# SPI_IFC.net
KiCad netlist of a schematic drawn in Altium Designer
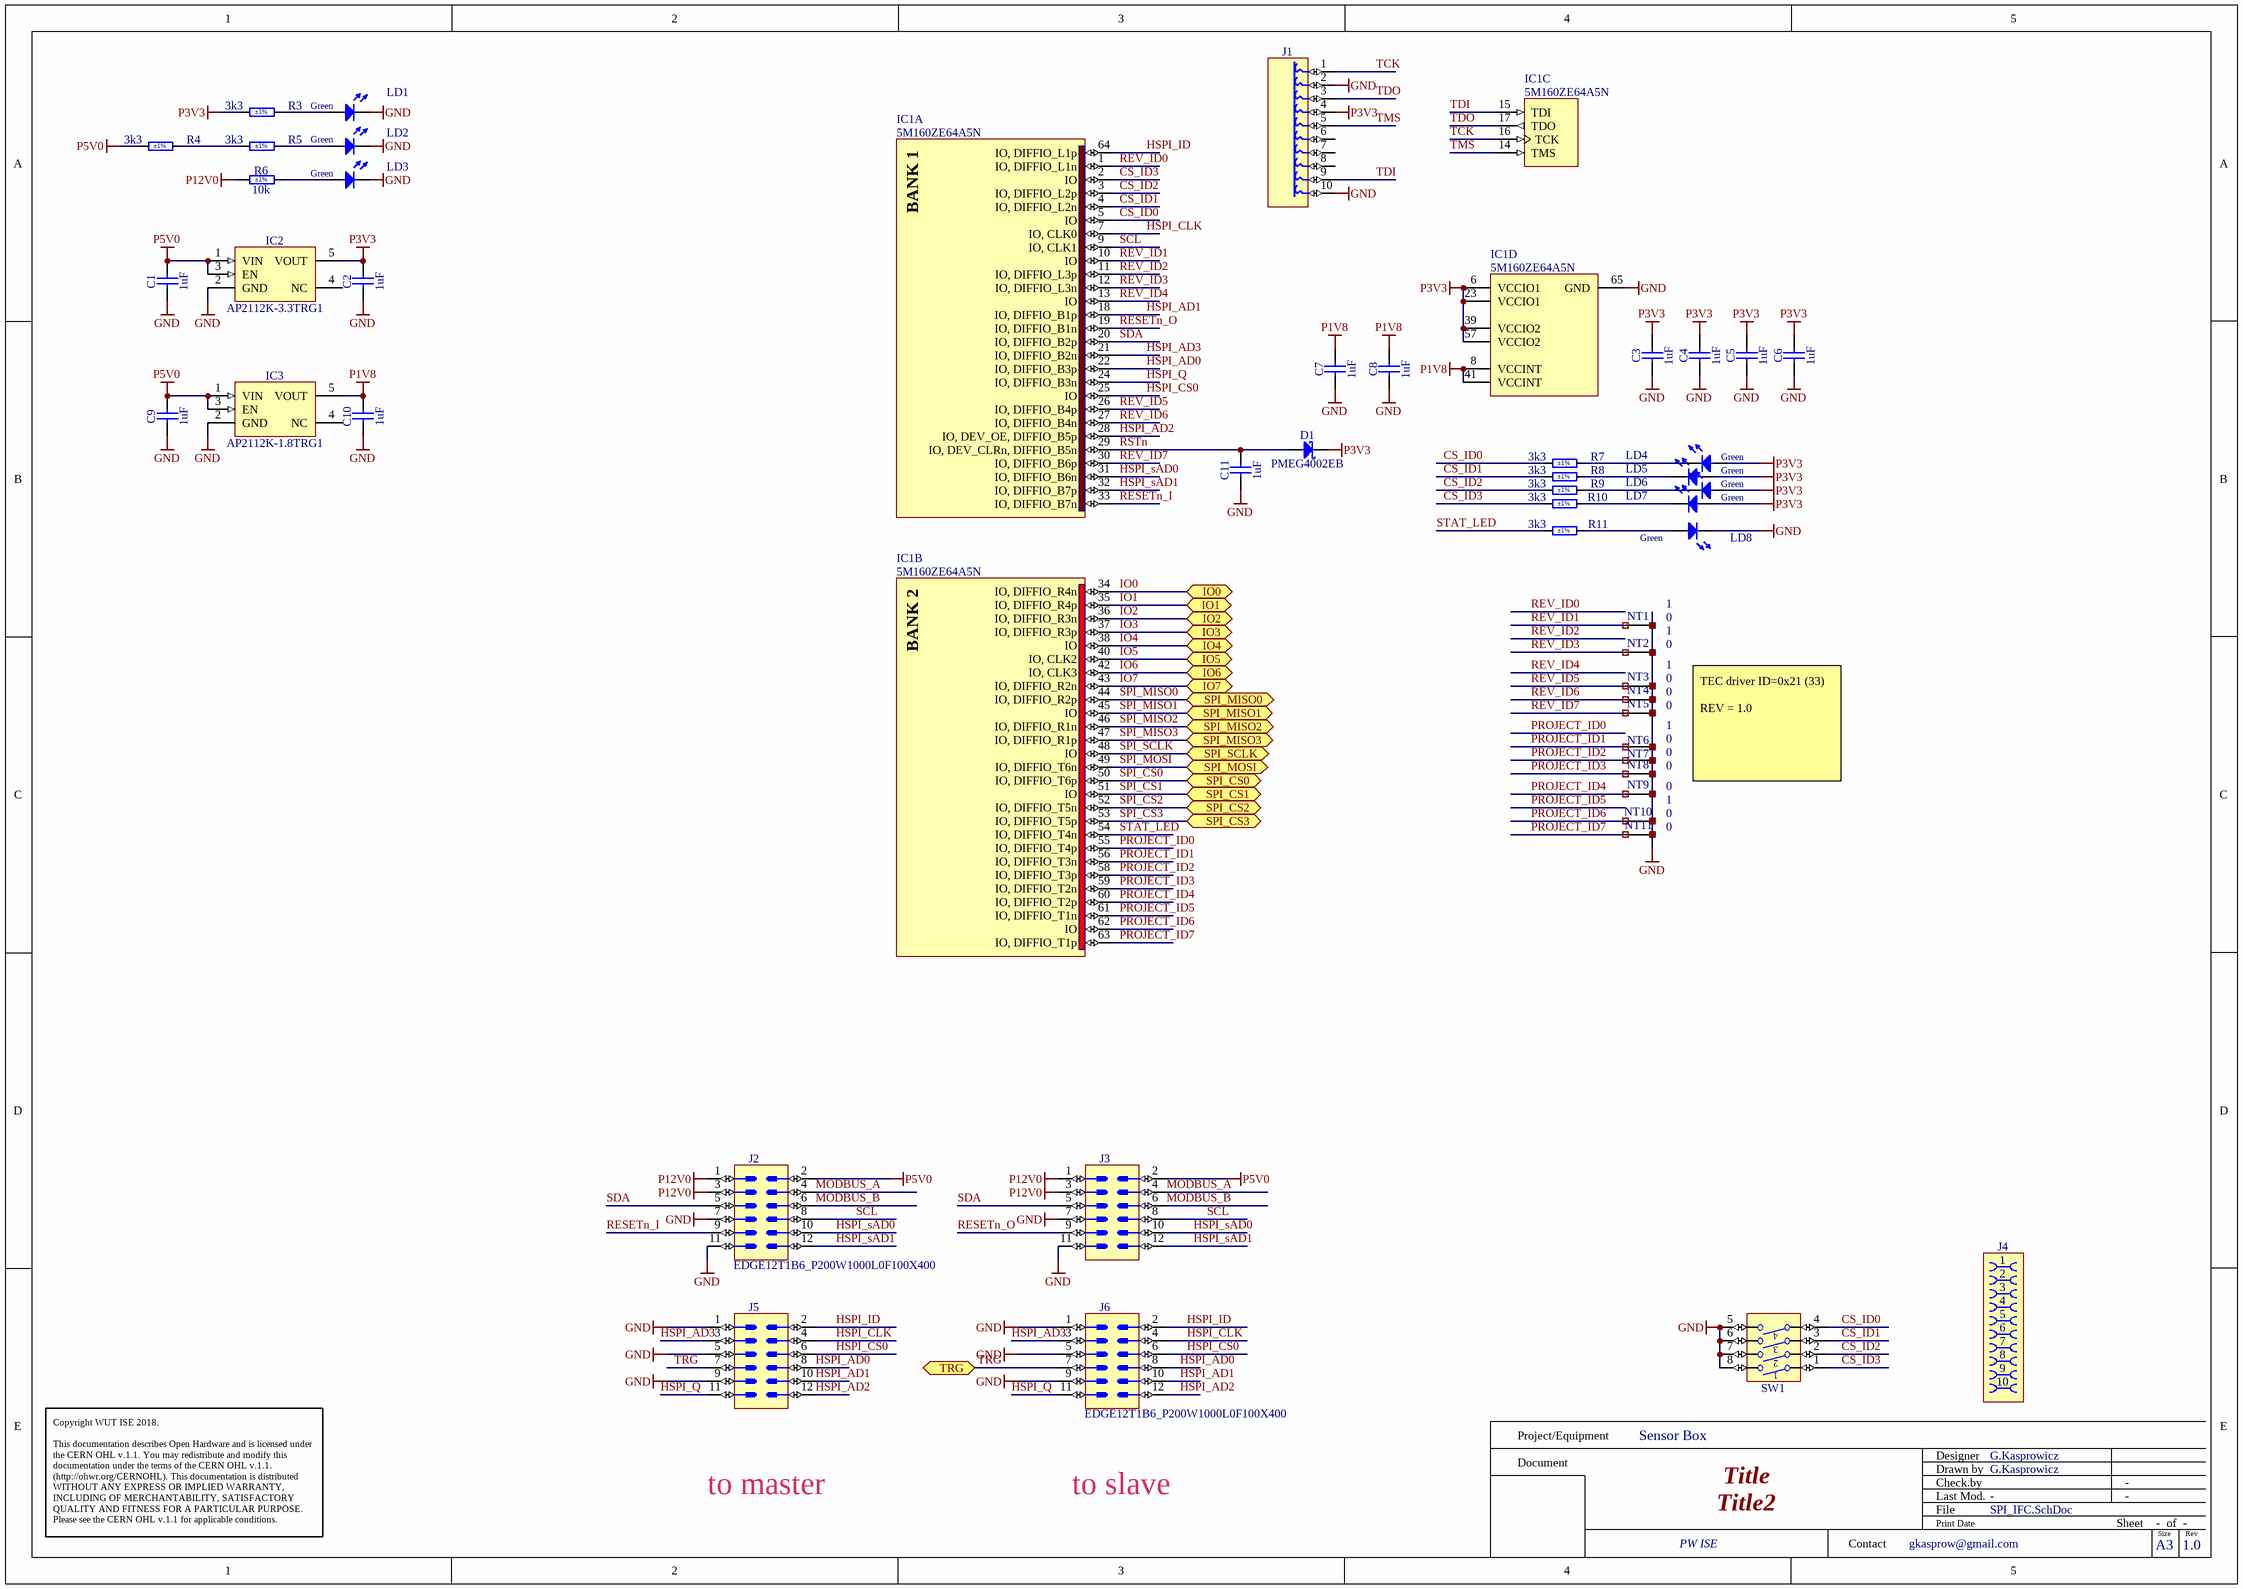
[diagram p0: SPI_IFC.SchDoc]

(export (version "E")
  (design (tool "Eeschema 10.0.6"))
  (components
    (comp (ref "C1")
      (value "1uF")
      (footprint "CAPC1005X55N")
      (description "Non-polarised capacitor")
      (fields
        (field (name "PART NUMBER") "CC0402_1UF_16V_10%_X5R")
        (field (name "VOLTAGE") "16V")
        (field (name "AUTHOR") "CERN DEM JLC")
      )
      (libsource (lib "Capacitors") (part "Capacitor - non polarized"))
    )
    (comp (ref "C2")
      (value "1uF")
      (footprint "CAPC1005X55N")
      (description "Non-polarised capacitor")
      (fields
        (field (name "PART NUMBER") "CC0402_1UF_16V_10%_X5R")
        (field (name "VOLTAGE") "16V")
        (field (name "AUTHOR") "CERN DEM JLC")
      )
      (libsource (lib "Capacitors") (part "Capacitor - non polarized"))
    )
    (comp (ref "C3")
      (value "1uF")
      (footprint "CAPC1005X55N")
      (description "Non-polarised capacitor")
      (fields
        (field (name "PART NUMBER") "CC0402_1UF_16V_10%_X5R")
        (field (name "VOLTAGE") "16V")
        (field (name "AUTHOR") "CERN DEM JLC")
      )
      (libsource (lib "Capacitors") (part "Capacitor - non polarized"))
    )
    (comp (ref "C4")
      (value "1uF")
      (footprint "CAPC1005X55N")
      (description "Non-polarised capacitor")
      (fields
        (field (name "PART NUMBER") "CC0402_1UF_16V_10%_X5R")
        (field (name "VOLTAGE") "16V")
        (field (name "AUTHOR") "CERN DEM JLC")
      )
      (libsource (lib "Capacitors") (part "Capacitor - non polarized"))
    )
    (comp (ref "C5")
      (value "1uF")
      (footprint "CAPC1005X55N")
      (description "Non-polarised capacitor")
      (fields
        (field (name "PART NUMBER") "CC0402_1UF_16V_10%_X5R")
        (field (name "VOLTAGE") "16V")
        (field (name "AUTHOR") "CERN DEM JLC")
      )
      (libsource (lib "Capacitors") (part "Capacitor - non polarized"))
    )
    (comp (ref "C6")
      (value "1uF")
      (footprint "CAPC1005X55N")
      (description "Non-polarised capacitor")
      (fields
        (field (name "PART NUMBER") "CC0402_1UF_16V_10%_X5R")
        (field (name "VOLTAGE") "16V")
        (field (name "AUTHOR") "CERN DEM JLC")
      )
      (libsource (lib "Capacitors") (part "Capacitor - non polarized"))
    )
    (comp (ref "C7")
      (value "1uF")
      (footprint "CAPC1005X55N")
      (description "Non-polarised capacitor")
      (fields
        (field (name "PART NUMBER") "CC0402_1UF_16V_10%_X5R")
        (field (name "VOLTAGE") "16V")
        (field (name "AUTHOR") "CERN DEM JLC")
      )
      (libsource (lib "Capacitors") (part "Capacitor - non polarized"))
    )
    (comp (ref "C8")
      (value "1uF")
      (footprint "CAPC1005X55N")
      (description "Non-polarised capacitor")
      (fields
        (field (name "PART NUMBER") "CC0402_1UF_16V_10%_X5R")
        (field (name "VOLTAGE") "16V")
        (field (name "AUTHOR") "CERN DEM JLC")
      )
      (libsource (lib "Capacitors") (part "Capacitor - non polarized"))
    )
    (comp (ref "C9")
      (value "1uF")
      (footprint "CAPC1005X55N")
      (description "Non-polarised capacitor")
      (fields
        (field (name "PART NUMBER") "CC0402_1UF_16V_10%_X5R")
        (field (name "VOLTAGE") "16V")
        (field (name "AUTHOR") "CERN DEM JLC")
      )
      (libsource (lib "Capacitors") (part "Capacitor - non polarized"))
    )
    (comp (ref "C10")
      (value "1uF")
      (footprint "CAPC1005X55N")
      (description "Non-polarised capacitor")
      (fields
        (field (name "PART NUMBER") "CC0402_1UF_16V_10%_X5R")
        (field (name "VOLTAGE") "16V")
        (field (name "AUTHOR") "CERN DEM JLC")
      )
      (libsource (lib "Capacitors") (part "Capacitor - non polarized"))
    )
    (comp (ref "C11")
      (value "1uF")
      (footprint "CAPC1005X55N")
      (description "Non-polarised capacitor")
      (fields
        (field (name "PART NUMBER") "CC0402_1UF_16V_10%_X5R")
        (field (name "VOLTAGE") "16V")
        (field (name "AUTHOR") "CERN DEM JLC")
      )
      (libsource (lib "Capacitors") (part "Capacitor - non polarized"))
    )
    (comp (ref "D1")
      (value "PMEG4002EB")
      (footprint "SODFL1608X65N")
      (description "Schottky Diode")
      (fields
        (field (name "VOLTAGE") "40V")
        (field (name "POWER") "200mA")
        (field (name "AUTHOR") "CERN DEM JMW")
      )
      (libsource (lib "ICs And Semiconductors") (part "Diode Schottky"))
    )
    (comp (ref "IC1")
      (value "5M160ZE64A5N")
      (footprint "QFP40P900X900X120-65N-S550")
      (fields (field (name "MANUFACTURER") "ALTERA") (field (name "AUTHOR") "CERN DEM JLC"))
      (libsource (lib "ICs And Semiconductors") (part "5M160ZE64A5N"))
    )
    (comp (ref "IC2")
      (value "AP2112K-3.3TRG1")
      (footprint "SOT95P285X140-5N")
      (description "600mA CMOS Low Dropout Linear Regulator with Enable")
      (fields
        (field (name "MANUFACTURER") "DIODES INCORPORATED")
        (field (name "MANUFACTURER PART NUMBER") "AP2112K-3.3")
        (field (name "AUTHOR") "CERN DEM MR")
      )
      (libsource (lib "ICs And Semiconductors") (part "AP2112K"))
    )
    (comp (ref "IC3")
      (value "AP2112K-1.8TRG1")
      (footprint "SOT95P285X140-5N")
      (description "600mA CMOS Low Dropout Linear Regulator with Enable")
      (fields
        (field (name "MANUFACTURER") "DIODES INCORPORATED")
        (field (name "MANUFACTURER PART NUMBER") "AP2112K-1.8")
        (field (name "AUTHOR") "CERN DEM JLC")
      )
      (libsource (lib "ICs And Semiconductors") (part "AP2112K"))
    )
    (comp (ref "J1")
      (value "TC2050-IDC")
      (footprint "TC2050-IDC")
      (description "TC2030-MCP and TC2050-IDC Pad Contact")
      (fields (field (name "AUTHOR") "CERN DEM HF"))
      (libsource (lib "Eletro-mechanical") (part "TC2050-IDC"))
    )
    (comp (ref "J2")
      (value "~")
      (footprint "EDGE12T1B6_P200W1000L0F100X400")
      (description "PCB Edge Connector 12 (2x6)")
      (fields
        (field (name "PART NUMBER") "EDGE10T1B6_P200W1000L0F100X400")
        (field (name "AUTHOR") "CERN DEM MR")
      )
      (libsource (lib "Connectors") (part "PCB Edge Connector 12 (2x6)"))
    )
    (comp (ref "J3")
      (value "~")
      (footprint "EDGE12T5B10_P200W1000L0F100X400")
      (description "PCB Edge Connector 12 (2x6)")
      (fields (field (name "PART NUMBER") "EDGE12T5B10_P200W1000L0F100X400") (field (name "AUTHOR") "GK"))
      (libsource (lib "Connectors") (part "PCB Edge Connector 12 (2x6) R"))
    )
    (comp (ref "J4")
      (value "~")
      (footprint "AVX_00 9159 010 061 916")
      (description "Open Ended Card Edge Connector, 9159 Series")
      (fields
        (field (name "PART NUMBER") "AVX_00 9159 010 061 916")
        (field (name "MANUFACTURER") "AVX")
        (field (name "AUTHOR") "CERN DEM MR")
      )
      (libsource (lib "Connectors") (part "AVX_00 9159 010 061 916"))
    )
    (comp (ref "J5")
      (value "~")
      (footprint "EDGE12T5B10_P200W1000L0F100X400")
      (description "PCB Edge Connector 12 (2x6)")
      (fields (field (name "PART NUMBER") "EDGE12T5B10_P200W1000L0F100X400") (field (name "AUTHOR") "GK"))
      (libsource (lib "Connectors") (part "PCB Edge Connector 12 (2x6) R"))
    )
    (comp (ref "J6")
      (value "~")
      (footprint "EDGE12T1B6_P200W1000L0F100X400")
      (description "PCB Edge Connector 12 (2x6)")
      (fields
        (field (name "PART NUMBER") "EDGE10T1B6_P200W1000L0F100X400")
        (field (name "AUTHOR") "CERN DEM MR")
      )
      (libsource (lib "Connectors") (part "PCB Edge Connector 12 (2x6)"))
    )
    (comp (ref "LD1")
      (value "Green")
      (footprint "LED_KINGBRIGHT_KP-1608CGCK")
      (description "LED Green 1C 2A")
      (fields
        (field (name "PART NUMBER") "LED_KINGBRIGHT_KP-1608CGCK")
        (field (name "MANUFACTURER") "KINGBRIGHT")
        (field (name "AUTHOR") "CERN DEM HF")
      )
      (libsource (lib "ICs And Semiconductors") (part "LED Green 1C 2A"))
    )
    (comp (ref "LD2")
      (value "Green")
      (footprint "LED_KINGBRIGHT_KP-1608CGCK")
      (description "LED Green 1C 2A")
      (fields
        (field (name "PART NUMBER") "LED_KINGBRIGHT_KP-1608CGCK")
        (field (name "MANUFACTURER") "KINGBRIGHT")
        (field (name "AUTHOR") "CERN DEM HF")
      )
      (libsource (lib "ICs And Semiconductors") (part "LED Green 1C 2A"))
    )
    (comp (ref "LD3")
      (value "Green")
      (footprint "LED_KINGBRIGHT_KP-1608CGCK")
      (description "LED Green 1C 2A")
      (fields
        (field (name "PART NUMBER") "LED_KINGBRIGHT_KP-1608CGCK")
        (field (name "MANUFACTURER") "KINGBRIGHT")
        (field (name "AUTHOR") "CERN DEM HF")
      )
      (libsource (lib "ICs And Semiconductors") (part "LED Green 1C 2A"))
    )
    (comp (ref "LD4")
      (value "Green")
      (footprint "LED_KINGBRIGHT_KP-1608CGCK")
      (description "LED Green 1C 2A")
      (fields
        (field (name "PART NUMBER") "LED_KINGBRIGHT_KP-1608CGCK")
        (field (name "MANUFACTURER") "KINGBRIGHT")
        (field (name "AUTHOR") "CERN DEM HF")
      )
      (libsource (lib "ICs And Semiconductors") (part "LED Green 1C 2A"))
    )
    (comp (ref "LD5")
      (value "Green")
      (footprint "LED_KINGBRIGHT_KP-1608CGCK")
      (description "LED Green 1C 2A")
      (fields
        (field (name "PART NUMBER") "LED_KINGBRIGHT_KP-1608CGCK")
        (field (name "MANUFACTURER") "KINGBRIGHT")
        (field (name "AUTHOR") "CERN DEM HF")
      )
      (libsource (lib "ICs And Semiconductors") (part "LED Green 1C 2A"))
    )
    (comp (ref "LD6")
      (value "Green")
      (footprint "LED_KINGBRIGHT_KP-1608CGCK")
      (description "LED Green 1C 2A")
      (fields
        (field (name "PART NUMBER") "LED_KINGBRIGHT_KP-1608CGCK")
        (field (name "MANUFACTURER") "KINGBRIGHT")
        (field (name "AUTHOR") "CERN DEM HF")
      )
      (libsource (lib "ICs And Semiconductors") (part "LED Green 1C 2A"))
    )
    (comp (ref "LD7")
      (value "Green")
      (footprint "LED_KINGBRIGHT_KP-1608CGCK")
      (description "LED Green 1C 2A")
      (fields
        (field (name "PART NUMBER") "LED_KINGBRIGHT_KP-1608CGCK")
        (field (name "MANUFACTURER") "KINGBRIGHT")
        (field (name "AUTHOR") "CERN DEM HF")
      )
      (libsource (lib "ICs And Semiconductors") (part "LED Green 1C 2A"))
    )
    (comp (ref "LD8")
      (value "Green")
      (footprint "LED_KINGBRIGHT_KP-1608CGCK")
      (description "LED Green 1C 2A")
      (fields
        (field (name "PART NUMBER") "LED_KINGBRIGHT_KP-1608CGCK")
        (field (name "MANUFACTURER") "KINGBRIGHT")
        (field (name "AUTHOR") "CERN DEM HF")
      )
      (libsource (lib "ICs And Semiconductors") (part "LED Green 1C 2A"))
    )
    (comp (ref "NT1")
      (value "Net Tie")
      (footprint "Net Tie 3")
      (fields (field (name "PART NUMBER") "Net Tie 3") (field (name "AUTHOR") "CERN DEM HF"))
      (libsource (lib "Eletro-mechanical") (part "Net Tie_a"))
    )
    (comp (ref "NT2")
      (value "Net Tie")
      (footprint "Net Tie 3")
      (fields (field (name "PART NUMBER") "Net Tie 3") (field (name "AUTHOR") "CERN DEM HF"))
      (libsource (lib "Eletro-mechanical") (part "Net Tie_a"))
    )
    (comp (ref "NT3")
      (value "Net Tie")
      (footprint "Net Tie 3")
      (fields (field (name "PART NUMBER") "Net Tie 3") (field (name "AUTHOR") "CERN DEM HF"))
      (libsource (lib "Eletro-mechanical") (part "Net Tie_a"))
    )
    (comp (ref "NT4")
      (value "Net Tie")
      (footprint "Net Tie 3")
      (fields (field (name "PART NUMBER") "Net Tie 3") (field (name "AUTHOR") "CERN DEM HF"))
      (libsource (lib "Eletro-mechanical") (part "Net Tie_a"))
    )
    (comp (ref "NT5")
      (value "Net Tie")
      (footprint "Net Tie 3")
      (fields (field (name "PART NUMBER") "Net Tie 3") (field (name "AUTHOR") "CERN DEM HF"))
      (libsource (lib "Eletro-mechanical") (part "Net Tie_a"))
    )
    (comp (ref "NT6")
      (value "Net Tie")
      (footprint "Net Tie 3")
      (fields (field (name "PART NUMBER") "Net Tie 3") (field (name "AUTHOR") "CERN DEM HF"))
      (libsource (lib "Eletro-mechanical") (part "Net Tie_a"))
    )
    (comp (ref "NT7")
      (value "Net Tie")
      (footprint "Net Tie 3")
      (fields (field (name "PART NUMBER") "Net Tie 3") (field (name "AUTHOR") "CERN DEM HF"))
      (libsource (lib "Eletro-mechanical") (part "Net Tie_a"))
    )
    (comp (ref "NT8")
      (value "Net Tie")
      (footprint "Net Tie 3")
      (fields (field (name "PART NUMBER") "Net Tie 3") (field (name "AUTHOR") "CERN DEM HF"))
      (libsource (lib "Eletro-mechanical") (part "Net Tie_a"))
    )
    (comp (ref "NT9")
      (value "Net Tie")
      (footprint "Net Tie 3")
      (fields (field (name "PART NUMBER") "Net Tie 3") (field (name "AUTHOR") "CERN DEM HF"))
      (libsource (lib "Eletro-mechanical") (part "Net Tie_a"))
    )
    (comp (ref "NT10")
      (value "Net Tie")
      (footprint "Net Tie 3")
      (fields (field (name "PART NUMBER") "Net Tie 3") (field (name "AUTHOR") "CERN DEM HF"))
      (libsource (lib "Eletro-mechanical") (part "Net Tie_a"))
    )
    (comp (ref "NT11")
      (value "Net Tie")
      (footprint "Net Tie 3")
      (fields (field (name "PART NUMBER") "Net Tie 3") (field (name "AUTHOR") "CERN DEM HF"))
      (libsource (lib "Eletro-mechanical") (part "Net Tie_a"))
    )
    (comp (ref "R3")
      (value "3k3")
      (footprint "RESC1005X40N")
      (description "Resistor - 1%")
      (fields
        (field (name "TOLERANCE") "±1%")
        (field (name "PART NUMBER") "R0402_3K3_1%_0.0625W_100PPM")
        (field (name "POWER") "0.0625W")
        (field (name "AUTHOR") "CERN DEM JLC")
      )
      (libsource (lib "Resistors") (part "Resistor - 1%"))
    )
    (comp (ref "R4")
      (value "3k3")
      (footprint "RESC1005X40N")
      (description "Resistor - 1%")
      (fields
        (field (name "TOLERANCE") "±1%")
        (field (name "PART NUMBER") "R0402_3K3_1%_0.0625W_100PPM")
        (field (name "POWER") "0.0625W")
        (field (name "AUTHOR") "CERN DEM JLC")
      )
      (libsource (lib "Resistors") (part "Resistor - 1%"))
    )
    (comp (ref "R5")
      (value "3k3")
      (footprint "RESC1005X40N")
      (description "Resistor - 1%")
      (fields
        (field (name "TOLERANCE") "±1%")
        (field (name "PART NUMBER") "R0402_3K3_1%_0.0625W_100PPM")
        (field (name "POWER") "0.0625W")
        (field (name "AUTHOR") "CERN DEM JLC")
      )
      (libsource (lib "Resistors") (part "Resistor - 1%"))
    )
    (comp (ref "R6")
      (value "10k")
      (footprint "RESC1005X40N")
      (description "Resistor - 1%")
      (fields
        (field (name "TOLERANCE") "±1%")
        (field (name "PART NUMBER") "R0402_10K_1%_0.0625W_100PPM")
        (field (name "POWER") "0.0625W")
        (field (name "AUTHOR") "CERN DEM JLC")
      )
      (libsource (lib "Resistors") (part "Resistor - 1%"))
    )
    (comp (ref "R7")
      (value "3k3")
      (footprint "RESC1005X40N")
      (description "Resistor - 1%")
      (fields
        (field (name "TOLERANCE") "±1%")
        (field (name "PART NUMBER") "R0402_3K3_1%_0.0625W_100PPM")
        (field (name "POWER") "0.0625W")
        (field (name "AUTHOR") "CERN DEM JLC")
      )
      (libsource (lib "Resistors") (part "Resistor - 1%"))
    )
    (comp (ref "R8")
      (value "3k3")
      (footprint "RESC1005X40N")
      (description "Resistor - 1%")
      (fields
        (field (name "TOLERANCE") "±1%")
        (field (name "PART NUMBER") "R0402_3K3_1%_0.0625W_100PPM")
        (field (name "POWER") "0.0625W")
        (field (name "AUTHOR") "CERN DEM JLC")
      )
      (libsource (lib "Resistors") (part "Resistor - 1%"))
    )
    (comp (ref "R9")
      (value "3k3")
      (footprint "RESC1005X40N")
      (description "Resistor - 1%")
      (fields
        (field (name "TOLERANCE") "±1%")
        (field (name "PART NUMBER") "R0402_3K3_1%_0.0625W_100PPM")
        (field (name "POWER") "0.0625W")
        (field (name "AUTHOR") "CERN DEM JLC")
      )
      (libsource (lib "Resistors") (part "Resistor - 1%"))
    )
    (comp (ref "R10")
      (value "3k3")
      (footprint "RESC1005X40N")
      (description "Resistor - 1%")
      (fields
        (field (name "TOLERANCE") "±1%")
        (field (name "PART NUMBER") "R0402_3K3_1%_0.0625W_100PPM")
        (field (name "POWER") "0.0625W")
        (field (name "AUTHOR") "CERN DEM JLC")
      )
      (libsource (lib "Resistors") (part "Resistor - 1%"))
    )
    (comp (ref "R11")
      (value "3k3")
      (footprint "RESC1005X40N")
      (description "Resistor - 1%")
      (fields
        (field (name "TOLERANCE") "±1%")
        (field (name "PART NUMBER") "R0402_3K3_1%_0.0625W_100PPM")
        (field (name "POWER") "0.0625W")
        (field (name "AUTHOR") "CERN DEM JLC")
      )
      (libsource (lib "Resistors") (part "Resistor - 1%"))
    )
    (comp (ref "SW1")
      (value "Switch")
      (footprint "SW_OMRON_A6H-4102")
      (description "4 Ways SPST DIP Switch")
      (fields
        (field (name "PART NUMBER") "SW_OMRON_A6H-4102")
        (field (name "MANUFACTURER") "OMRON")
        (field (name "AUTHOR") "CERN DEM JLC")
      )
      (libsource (lib "Eletro-mechanical") (part "SW 4x SPST DIP Switch"))
    )
  )
  (nets
    (net (code "1") (name "/CS_ID0") (class "Default")
      (node (ref "IC1") (pin "5") (pinfunction "IO_5") (pintype "bidirectional"))
      (node (ref "R7") (pin "2") (pinfunction "2_2") (pintype "passive"))
      (node (ref "SW1") (pin "4") (pinfunction "4_4") (pintype "bidirectional"))
    )
    (net (code "2") (name "/CS_ID1") (class "Default")
      (node (ref "IC1") (pin "4") (pinfunction "IO,_DIFFIO_L2n_4") (pintype "bidirectional"))
      (node (ref "R8") (pin "2") (pinfunction "2_2") (pintype "passive"))
      (node (ref "SW1") (pin "3") (pinfunction "3_3") (pintype "bidirectional"))
    )
    (net (code "3") (name "/CS_ID2") (class "Default")
      (node (ref "IC1") (pin "3") (pinfunction "IO,_DIFFIO_L2p_3") (pintype "bidirectional"))
      (node (ref "R9") (pin "2") (pinfunction "2_2") (pintype "passive"))
      (node (ref "SW1") (pin "2") (pinfunction "2_2") (pintype "bidirectional"))
    )
    (net (code "4") (name "/CS_ID3") (class "Default")
      (node (ref "IC1") (pin "2") (pinfunction "IO_2") (pintype "bidirectional"))
      (node (ref "R10") (pin "2") (pinfunction "2_2") (pintype "passive"))
      (node (ref "SW1") (pin "1") (pinfunction "1_1") (pintype "bidirectional"))
    )
    (net (code "5") (name "/HSPI_AD0") (class "Default")
      (node (ref "IC1") (pin "22") (pinfunction "IO,_DIFFIO_B3p_22") (pintype "bidirectional"))
      (node (ref "J5") (pin "8") (pinfunction "8_8") (pintype "bidirectional"))
      (node (ref "J6") (pin "8") (pinfunction "8_8") (pintype "bidirectional"))
    )
    (net (code "6") (name "/HSPI_AD1") (class "Default")
      (node (ref "IC1") (pin "18") (pinfunction "IO,_DIFFIO_B1p_18") (pintype "bidirectional"))
      (node (ref "J5") (pin "10") (pinfunction "10_10") (pintype "bidirectional"))
      (node (ref "J6") (pin "10") (pinfunction "10_10") (pintype "bidirectional"))
    )
    (net (code "7") (name "/HSPI_AD2") (class "Default")
      (node (ref "IC1") (pin "28") (pinfunction "IO,_DEV_OE,_DIFFIO_B5p_28") (pintype "bidirectional"))
      (node (ref "J5") (pin "12") (pinfunction "12_12") (pintype "bidirectional"))
      (node (ref "J6") (pin "12") (pinfunction "12_12") (pintype "bidirectional"))
    )
    (net (code "8") (name "/HSPI_AD3") (class "Default")
      (node (ref "IC1") (pin "21") (pinfunction "IO,_DIFFIO_B2n_21") (pintype "bidirectional"))
      (node (ref "J5") (pin "3") (pinfunction "3_3") (pintype "bidirectional"))
      (node (ref "J6") (pin "3") (pinfunction "3_3") (pintype "bidirectional"))
    )
    (net (code "9") (name "/HSPI_CLK") (class "Default")
      (node (ref "IC1") (pin "7") (pinfunction "IO,_CLK0_7") (pintype "bidirectional"))
      (node (ref "J5") (pin "4") (pinfunction "4_4") (pintype "bidirectional"))
      (node (ref "J6") (pin "4") (pinfunction "4_4") (pintype "bidirectional"))
    )
    (net (code "10") (name "/HSPI_CS0") (class "Default")
      (node (ref "IC1") (pin "25") (pinfunction "IO_25") (pintype "bidirectional"))
      (node (ref "J5") (pin "6") (pinfunction "6_6") (pintype "bidirectional"))
      (node (ref "J6") (pin "6") (pinfunction "6_6") (pintype "bidirectional"))
    )
    (net (code "11") (name "/HSPI_ID") (class "Default")
      (node (ref "IC1") (pin "64") (pinfunction "IO,_DIFFIO_L1p_64") (pintype "bidirectional"))
      (node (ref "J5") (pin "2") (pinfunction "2_2") (pintype "bidirectional"))
      (node (ref "J6") (pin "2") (pinfunction "2_2") (pintype "bidirectional"))
    )
    (net (code "12") (name "/HSPI_Q") (class "Default")
      (node (ref "IC1") (pin "24") (pinfunction "IO,_DIFFIO_B3n_24") (pintype "bidirectional"))
      (node (ref "J5") (pin "11") (pinfunction "11_11") (pintype "bidirectional"))
      (node (ref "J6") (pin "11") (pinfunction "11_11") (pintype "bidirectional"))
    )
    (net (code "13") (name "/HSPI_sAD0") (class "Default")
      (node (ref "IC1") (pin "31") (pinfunction "IO,_DIFFIO_B6n_31") (pintype "bidirectional"))
      (node (ref "J2") (pin "10") (pinfunction "10_10") (pintype "bidirectional"))
      (node (ref "J3") (pin "10") (pinfunction "10_10") (pintype "bidirectional"))
    )
    (net (code "14") (name "/HSPI_sAD1") (class "Default")
      (node (ref "IC1") (pin "32") (pinfunction "IO,_DIFFIO_B7p_32") (pintype "bidirectional"))
      (node (ref "J2") (pin "12") (pinfunction "12_12") (pintype "bidirectional"))
      (node (ref "J3") (pin "12") (pinfunction "12_12") (pintype "bidirectional"))
    )
    (net (code "15") (name "/IO0") (class "Default")
      (node (ref "IC1") (pin "34") (pinfunction "IO,_DIFFIO_R4n_34") (pintype "bidirectional"))
    )
    (net (code "16") (name "/IO1") (class "Default")
      (node (ref "IC1") (pin "35") (pinfunction "IO,_DIFFIO_R4p_35") (pintype "bidirectional"))
    )
    (net (code "17") (name "/IO2") (class "Default")
      (node (ref "IC1") (pin "36") (pinfunction "IO,_DIFFIO_R3n_36") (pintype "bidirectional"))
    )
    (net (code "18") (name "/IO3") (class "Default")
      (node (ref "IC1") (pin "37") (pinfunction "IO,_DIFFIO_R3p_37") (pintype "bidirectional"))
    )
    (net (code "19") (name "/IO4") (class "Default")
      (node (ref "IC1") (pin "38") (pinfunction "IO_38") (pintype "bidirectional"))
    )
    (net (code "20") (name "/IO5") (class "Default")
      (node (ref "IC1") (pin "40") (pinfunction "IO,_CLK2_40") (pintype "bidirectional"))
    )
    (net (code "21") (name "/IO6") (class "Default")
      (node (ref "IC1") (pin "42") (pinfunction "IO,_CLK3_42") (pintype "bidirectional"))
    )
    (net (code "22") (name "/IO7") (class "Default")
      (node (ref "IC1") (pin "43") (pinfunction "IO,_DIFFIO_R2n_43") (pintype "bidirectional"))
    )
    (net (code "23") (name "/MODBUS_A") (class "Default")
      (node (ref "J2") (pin "4") (pinfunction "4_4") (pintype "bidirectional"))
      (node (ref "J3") (pin "4") (pinfunction "4_4") (pintype "bidirectional"))
    )
    (net (code "24") (name "/MODBUS_B") (class "Default")
      (node (ref "J2") (pin "6") (pinfunction "6_6") (pintype "bidirectional"))
      (node (ref "J3") (pin "6") (pinfunction "6_6") (pintype "bidirectional"))
    )
    (net (code "25") (name "/PROJECT_ID0") (class "Default")
      (node (ref "IC1") (pin "55") (pinfunction "IO,_DIFFIO_T4p_55") (pintype "bidirectional"))
    )
    (net (code "26") (name "/PROJECT_ID1") (class "Default")
      (node (ref "IC1") (pin "56") (pinfunction "IO,_DIFFIO_T3n_56") (pintype "bidirectional"))
      (node (ref "NT6") (pin "1") (pinfunction "1_1") (pintype "bidirectional"))
    )
    (net (code "27") (name "/PROJECT_ID2") (class "Default")
      (node (ref "IC1") (pin "58") (pinfunction "IO,_DIFFIO_T3p_58") (pintype "bidirectional"))
      (node (ref "NT7") (pin "1") (pinfunction "1_1") (pintype "bidirectional"))
    )
    (net (code "28") (name "/PROJECT_ID3") (class "Default")
      (node (ref "IC1") (pin "59") (pinfunction "IO,_DIFFIO_T2n_59") (pintype "bidirectional"))
      (node (ref "NT8") (pin "1") (pinfunction "1_1") (pintype "bidirectional"))
    )
    (net (code "29") (name "/PROJECT_ID4") (class "Default")
      (node (ref "IC1") (pin "60") (pinfunction "IO,_DIFFIO_T2p_60") (pintype "bidirectional"))
      (node (ref "NT9") (pin "1") (pinfunction "1_1") (pintype "bidirectional"))
    )
    (net (code "30") (name "/PROJECT_ID5") (class "Default")
      (node (ref "IC1") (pin "61") (pinfunction "IO,_DIFFIO_T1n_61") (pintype "bidirectional"))
    )
    (net (code "31") (name "/PROJECT_ID6") (class "Default")
      (node (ref "IC1") (pin "62") (pinfunction "IO_62") (pintype "bidirectional"))
      (node (ref "NT10") (pin "1") (pinfunction "1_1") (pintype "bidirectional"))
    )
    (net (code "32") (name "/PROJECT_ID7") (class "Default")
      (node (ref "IC1") (pin "63") (pinfunction "IO,_DIFFIO_T1p_63") (pintype "bidirectional"))
      (node (ref "NT11") (pin "1") (pinfunction "1_1") (pintype "bidirectional"))
    )
    (net (code "33") (name "/RESETn_I") (class "Default")
      (node (ref "IC1") (pin "33") (pinfunction "IO,_DIFFIO_B7n_33") (pintype "bidirectional"))
      (node (ref "J2") (pin "9") (pinfunction "9_9") (pintype "bidirectional"))
    )
    (net (code "34") (name "/RESETn_O") (class "Default")
      (node (ref "IC1") (pin "19") (pinfunction "IO,_DIFFIO_B1n_19") (pintype "bidirectional"))
      (node (ref "J3") (pin "9") (pinfunction "9_9") (pintype "bidirectional"))
    )
    (net (code "35") (name "/REV_ID0") (class "Default")
      (node (ref "IC1") (pin "1") (pinfunction "IO,_DIFFIO_L1n_1") (pintype "bidirectional"))
    )
    (net (code "36") (name "/REV_ID1") (class "Default")
      (node (ref "IC1") (pin "10") (pinfunction "IO_10") (pintype "bidirectional"))
      (node (ref "NT1") (pin "1") (pinfunction "1_1") (pintype "bidirectional"))
    )
    (net (code "37") (name "/REV_ID2") (class "Default")
      (node (ref "IC1") (pin "11") (pinfunction "IO,_DIFFIO_L3p_11") (pintype "bidirectional"))
    )
    (net (code "38") (name "/REV_ID3") (class "Default")
      (node (ref "IC1") (pin "12") (pinfunction "IO,_DIFFIO_L3n_12") (pintype "bidirectional"))
      (node (ref "NT2") (pin "1") (pinfunction "1_1") (pintype "bidirectional"))
    )
    (net (code "39") (name "/REV_ID4") (class "Default")
      (node (ref "IC1") (pin "13") (pinfunction "IO_13") (pintype "bidirectional"))
    )
    (net (code "40") (name "/REV_ID5") (class "Default")
      (node (ref "IC1") (pin "26") (pinfunction "IO,_DIFFIO_B4p_26") (pintype "bidirectional"))
      (node (ref "NT3") (pin "1") (pinfunction "1_1") (pintype "bidirectional"))
    )
    (net (code "41") (name "/REV_ID6") (class "Default")
      (node (ref "IC1") (pin "27") (pinfunction "IO,_DIFFIO_B4n_27") (pintype "bidirectional"))
      (node (ref "NT4") (pin "1") (pinfunction "1_1") (pintype "bidirectional"))
    )
    (net (code "42") (name "/REV_ID7") (class "Default")
      (node (ref "IC1") (pin "30") (pinfunction "IO,_DIFFIO_B6p_30") (pintype "bidirectional"))
      (node (ref "NT5") (pin "1") (pinfunction "1_1") (pintype "bidirectional"))
    )
    (net (code "43") (name "/RSTn") (class "Default")
      (node (ref "C11") (pin "2") (pinfunction "2_2") (pintype "passive"))
      (node (ref "D1") (pin "2") (pinfunction "A_2") (pintype "passive"))
      (node (ref "IC1") (pin "29") (pinfunction "IO,_DEV_CLRn,_DIFFIO_B5n_29") (pintype "bidirectional"))
    )
    (net (code "44") (name "/SCL") (class "Default")
      (node (ref "IC1") (pin "9") (pinfunction "IO,_CLK1_9") (pintype "bidirectional"))
      (node (ref "J2") (pin "8") (pinfunction "8_8") (pintype "bidirectional"))
      (node (ref "J3") (pin "8") (pinfunction "8_8") (pintype "bidirectional"))
    )
    (net (code "45") (name "/SDA") (class "Default")
      (node (ref "IC1") (pin "20") (pinfunction "IO,_DIFFIO_B2p_20") (pintype "bidirectional"))
      (node (ref "J2") (pin "5") (pinfunction "5_5") (pintype "bidirectional"))
      (node (ref "J3") (pin "5") (pinfunction "5_5") (pintype "bidirectional"))
    )
    (net (code "46") (name "/SPI_CS0") (class "Default")
      (node (ref "IC1") (pin "50") (pinfunction "IO,_DIFFIO_T6p_50") (pintype "bidirectional"))
    )
    (net (code "47") (name "/SPI_CS1") (class "Default")
      (node (ref "IC1") (pin "51") (pinfunction "IO_51") (pintype "bidirectional"))
    )
    (net (code "48") (name "/SPI_CS2") (class "Default")
      (node (ref "IC1") (pin "52") (pinfunction "IO,_DIFFIO_T5n_52") (pintype "bidirectional"))
    )
    (net (code "49") (name "/SPI_CS3") (class "Default")
      (node (ref "IC1") (pin "53") (pinfunction "IO,_DIFFIO_T5p_53") (pintype "bidirectional"))
    )
    (net (code "50") (name "/SPI_MISO0") (class "Default")
      (node (ref "IC1") (pin "44") (pinfunction "IO,_DIFFIO_R2p_44") (pintype "bidirectional"))
    )
    (net (code "51") (name "/SPI_MISO1") (class "Default")
      (node (ref "IC1") (pin "45") (pinfunction "IO_45") (pintype "bidirectional"))
    )
    (net (code "52") (name "/SPI_MISO2") (class "Default")
      (node (ref "IC1") (pin "46") (pinfunction "IO,_DIFFIO_R1n_46") (pintype "bidirectional"))
    )
    (net (code "53") (name "/SPI_MISO3") (class "Default")
      (node (ref "IC1") (pin "47") (pinfunction "IO,_DIFFIO_R1p_47") (pintype "bidirectional"))
    )
    (net (code "54") (name "/SPI_MOSI") (class "Default")
      (node (ref "IC1") (pin "49") (pinfunction "IO,_DIFFIO_T6n_49") (pintype "bidirectional"))
    )
    (net (code "55") (name "/SPI_SCLK") (class "Default")
      (node (ref "IC1") (pin "48") (pinfunction "IO_48") (pintype "bidirectional"))
    )
    (net (code "56") (name "/STAT_LED") (class "Default")
      (node (ref "IC1") (pin "54") (pinfunction "IO,_DIFFIO_T4n_54") (pintype "bidirectional"))
      (node (ref "R11") (pin "2") (pinfunction "2_2") (pintype "passive"))
    )
    (net (code "57") (name "/TCK") (class "Default")
      (node (ref "IC1") (pin "16") (pinfunction "TCK_16") (pintype "input"))
      (node (ref "J1") (pin "1") (pinfunction "1_1") (pintype "bidirectional"))
    )
    (net (code "58") (name "/TDI") (class "Default")
      (node (ref "IC1") (pin "15") (pinfunction "TDI_15") (pintype "input"))
      (node (ref "J1") (pin "9") (pinfunction "9_9") (pintype "bidirectional"))
    )
    (net (code "59") (name "/TDO") (class "Default")
      (node (ref "IC1") (pin "17") (pinfunction "TDO_17") (pintype "output"))
      (node (ref "J1") (pin "3") (pinfunction "3_3") (pintype "bidirectional"))
    )
    (net (code "60") (name "/TMS") (class "Default")
      (node (ref "IC1") (pin "14") (pinfunction "TMS_14") (pintype "input"))
      (node (ref "J1") (pin "5") (pinfunction "5_5") (pintype "bidirectional"))
    )
    (net (code "61") (name "/TRG") (class "Default")
      (node (ref "J5") (pin "7") (pinfunction "7_7") (pintype "bidirectional"))
      (node (ref "J6") (pin "7") (pinfunction "7_7") (pintype "bidirectional"))
    )
    (net (code "62") (name "GND") (class "Default")
      (node (ref "C1") (pin "1") (pinfunction "1_1") (pintype "passive"))
      (node (ref "C10") (pin "1") (pinfunction "1_1") (pintype "passive"))
      (node (ref "C11") (pin "1") (pinfunction "1_1") (pintype "passive"))
      (node (ref "C2") (pin "1") (pinfunction "1_1") (pintype "passive"))
      (node (ref "C3") (pin "1") (pinfunction "1_1") (pintype "passive"))
      (node (ref "C4") (pin "1") (pinfunction "1_1") (pintype "passive"))
      (node (ref "C5") (pin "1") (pinfunction "1_1") (pintype "passive"))
      (node (ref "C6") (pin "1") (pinfunction "1_1") (pintype "passive"))
      (node (ref "C7") (pin "1") (pinfunction "1_1") (pintype "passive"))
      (node (ref "C8") (pin "1") (pinfunction "1_1") (pintype "passive"))
      (node (ref "C9") (pin "1") (pinfunction "1_1") (pintype "passive"))
      (node (ref "IC1") (pin "65") (pinfunction "GND_65") (pintype "power_in"))
      (node (ref "IC2") (pin "2") (pinfunction "GND_2") (pintype "power_in"))
      (node (ref "IC3") (pin "2") (pinfunction "GND_2") (pintype "power_in"))
      (node (ref "J1") (pin "10") (pinfunction "10_10") (pintype "bidirectional"))
      (node (ref "J1") (pin "2") (pinfunction "2_2") (pintype "bidirectional"))
      (node (ref "J2") (pin "11") (pinfunction "11_11") (pintype "bidirectional"))
      (node (ref "J2") (pin "7") (pinfunction "7_7") (pintype "bidirectional"))
      (node (ref "J3") (pin "11") (pinfunction "11_11") (pintype "bidirectional"))
      (node (ref "J3") (pin "7") (pinfunction "7_7") (pintype "bidirectional"))
      (node (ref "J5") (pin "1") (pinfunction "1_1") (pintype "bidirectional"))
      (node (ref "J5") (pin "5") (pinfunction "5_5") (pintype "bidirectional"))
      (node (ref "J5") (pin "9") (pinfunction "9_9") (pintype "bidirectional"))
      (node (ref "J6") (pin "1") (pinfunction "1_1") (pintype "bidirectional"))
      (node (ref "J6") (pin "5") (pinfunction "5_5") (pintype "bidirectional"))
      (node (ref "J6") (pin "9") (pinfunction "9_9") (pintype "bidirectional"))
      (node (ref "LD1") (pin "1") (pinfunction "C_1") (pintype "passive"))
      (node (ref "LD2") (pin "1") (pinfunction "C_1") (pintype "passive"))
      (node (ref "LD3") (pin "1") (pinfunction "C_1") (pintype "passive"))
      (node (ref "LD8") (pin "1") (pinfunction "C_1") (pintype "passive"))
      (node (ref "NT1") (pin "2") (pinfunction "2_2") (pintype "bidirectional"))
      (node (ref "NT10") (pin "2") (pinfunction "2_2") (pintype "bidirectional"))
      (node (ref "NT11") (pin "2") (pinfunction "2_2") (pintype "bidirectional"))
      (node (ref "NT2") (pin "2") (pinfunction "2_2") (pintype "bidirectional"))
      (node (ref "NT3") (pin "2") (pinfunction "2_2") (pintype "bidirectional"))
      (node (ref "NT4") (pin "2") (pinfunction "2_2") (pintype "bidirectional"))
      (node (ref "NT5") (pin "2") (pinfunction "2_2") (pintype "bidirectional"))
      (node (ref "NT6") (pin "2") (pinfunction "2_2") (pintype "bidirectional"))
      (node (ref "NT7") (pin "2") (pinfunction "2_2") (pintype "bidirectional"))
      (node (ref "NT8") (pin "2") (pinfunction "2_2") (pintype "bidirectional"))
      (node (ref "NT9") (pin "2") (pinfunction "2_2") (pintype "bidirectional"))
      (node (ref "SW1") (pin "5") (pinfunction "5_5") (pintype "bidirectional"))
      (node (ref "SW1") (pin "6") (pinfunction "6_6") (pintype "bidirectional"))
      (node (ref "SW1") (pin "7") (pinfunction "7_7") (pintype "bidirectional"))
      (node (ref "SW1") (pin "8") (pinfunction "8_8") (pintype "bidirectional"))
    )
    (net (code "63") (name "Net-(LD1-A)") (class "Default")
      (node (ref "LD1") (pin "2") (pinfunction "A_2") (pintype "passive"))
      (node (ref "R3") (pin "1") (pinfunction "1_1") (pintype "passive"))
    )
    (net (code "64") (name "Net-(LD2-A)") (class "Default")
      (node (ref "LD2") (pin "2") (pinfunction "A_2") (pintype "passive"))
      (node (ref "R5") (pin "1") (pinfunction "1_1") (pintype "passive"))
    )
    (net (code "65") (name "Net-(LD3-A)") (class "Default")
      (node (ref "LD3") (pin "2") (pinfunction "A_2") (pintype "passive"))
      (node (ref "R6") (pin "2") (pinfunction "2_2") (pintype "passive"))
    )
    (net (code "66") (name "Net-(LD4-C)") (class "Default")
      (node (ref "LD4") (pin "1") (pinfunction "C_1") (pintype "passive"))
      (node (ref "R7") (pin "1") (pinfunction "1_1") (pintype "passive"))
    )
    (net (code "67") (name "Net-(LD5-C)") (class "Default")
      (node (ref "LD5") (pin "1") (pinfunction "C_1") (pintype "passive"))
      (node (ref "R8") (pin "1") (pinfunction "1_1") (pintype "passive"))
    )
    (net (code "68") (name "Net-(LD6-C)") (class "Default")
      (node (ref "LD6") (pin "1") (pinfunction "C_1") (pintype "passive"))
      (node (ref "R9") (pin "1") (pinfunction "1_1") (pintype "passive"))
    )
    (net (code "69") (name "Net-(LD7-C)") (class "Default")
      (node (ref "LD7") (pin "1") (pinfunction "C_1") (pintype "passive"))
      (node (ref "R10") (pin "1") (pinfunction "1_1") (pintype "passive"))
    )
    (net (code "70") (name "Net-(LD8-A)") (class "Default")
      (node (ref "LD8") (pin "2") (pinfunction "A_2") (pintype "passive"))
      (node (ref "R11") (pin "1") (pinfunction "1_1") (pintype "passive"))
    )
    (net (code "71") (name "Net-(R4-Pad1)") (class "Default")
      (node (ref "R4") (pin "1") (pinfunction "1_1") (pintype "passive"))
      (node (ref "R5") (pin "2") (pinfunction "2_2") (pintype "passive"))
    )
    (net (code "72") (name "P1V8") (class "Default")
      (node (ref "C10") (pin "2") (pinfunction "2_2") (pintype "passive"))
      (node (ref "C7") (pin "2") (pinfunction "2_2") (pintype "passive"))
      (node (ref "C8") (pin "2") (pinfunction "2_2") (pintype "passive"))
      (node (ref "IC1") (pin "41") (pinfunction "VCCINT_41") (pintype "power_in"))
      (node (ref "IC1") (pin "8") (pinfunction "VCCINT_8") (pintype "power_in"))
      (node (ref "IC3") (pin "5") (pinfunction "VOUT_5") (pintype "power_in"))
    )
    (net (code "73") (name "P3V3") (class "Default")
      (node (ref "C2") (pin "2") (pinfunction "2_2") (pintype "passive"))
      (node (ref "C3") (pin "2") (pinfunction "2_2") (pintype "passive"))
      (node (ref "C4") (pin "2") (pinfunction "2_2") (pintype "passive"))
      (node (ref "C5") (pin "2") (pinfunction "2_2") (pintype "passive"))
      (node (ref "C6") (pin "2") (pinfunction "2_2") (pintype "passive"))
      (node (ref "D1") (pin "1") (pinfunction "C_1") (pintype "passive"))
      (node (ref "IC1") (pin "23") (pinfunction "VCCIO1_23") (pintype "power_in"))
      (node (ref "IC1") (pin "39") (pinfunction "VCCIO2_39") (pintype "power_in"))
      (node (ref "IC1") (pin "57") (pinfunction "VCCIO2_57") (pintype "power_in"))
      (node (ref "IC1") (pin "6") (pinfunction "VCCIO1_6") (pintype "power_in"))
      (node (ref "IC2") (pin "5") (pinfunction "VOUT_5") (pintype "power_in"))
      (node (ref "J1") (pin "4") (pinfunction "4_4") (pintype "bidirectional"))
      (node (ref "LD4") (pin "2") (pinfunction "A_2") (pintype "passive"))
      (node (ref "LD5") (pin "2") (pinfunction "A_2") (pintype "passive"))
      (node (ref "LD6") (pin "2") (pinfunction "A_2") (pintype "passive"))
      (node (ref "LD7") (pin "2") (pinfunction "A_2") (pintype "passive"))
      (node (ref "R3") (pin "2") (pinfunction "2_2") (pintype "passive"))
    )
    (net (code "74") (name "P5V0") (class "Default")
      (node (ref "C1") (pin "2") (pinfunction "2_2") (pintype "passive"))
      (node (ref "C9") (pin "2") (pinfunction "2_2") (pintype "passive"))
      (node (ref "IC2") (pin "1") (pinfunction "VIN_1") (pintype "input"))
      (node (ref "IC2") (pin "3") (pinfunction "EN_3") (pintype "input"))
      (node (ref "IC3") (pin "1") (pinfunction "VIN_1") (pintype "input"))
      (node (ref "IC3") (pin "3") (pinfunction "EN_3") (pintype "input"))
      (node (ref "J2") (pin "2") (pinfunction "2_2") (pintype "bidirectional"))
      (node (ref "J3") (pin "2") (pinfunction "2_2") (pintype "bidirectional"))
      (node (ref "R4") (pin "2") (pinfunction "2_2") (pintype "passive"))
    )
    (net (code "75") (name "P12V0") (class "Default")
      (node (ref "J2") (pin "1") (pinfunction "1_1") (pintype "bidirectional"))
      (node (ref "J2") (pin "3") (pinfunction "3_3") (pintype "bidirectional"))
      (node (ref "J3") (pin "1") (pinfunction "1_1") (pintype "bidirectional"))
      (node (ref "J3") (pin "3") (pinfunction "3_3") (pintype "bidirectional"))
      (node (ref "R6") (pin "1") (pinfunction "1_1") (pintype "passive"))
    )
    (net (code "76") (name "unconnected-(IC2-NC-Pad4)") (class "Default")
      (node (ref "IC2") (pin "4") (pinfunction "NC_4") (pintype "passive"))
    )
    (net (code "77") (name "unconnected-(IC3-NC-Pad4)") (class "Default")
      (node (ref "IC3") (pin "4") (pinfunction "NC_4") (pintype "passive"))
    )
    (net (code "78") (name "unconnected-(J1-Pad6)") (class "Default")
      (node (ref "J1") (pin "6") (pinfunction "6_6") (pintype "bidirectional"))
    )
    (net (code "79") (name "unconnected-(J1-Pad7)") (class "Default")
      (node (ref "J1") (pin "7") (pinfunction "7_7") (pintype "bidirectional"))
    )
    (net (code "80") (name "unconnected-(J1-Pad8)") (class "Default")
      (node (ref "J1") (pin "8") (pinfunction "8_8") (pintype "bidirectional"))
    )
  )
)
